# ExternalMotorController.net
KiCad netlist of a schematic drawn in EAGLE
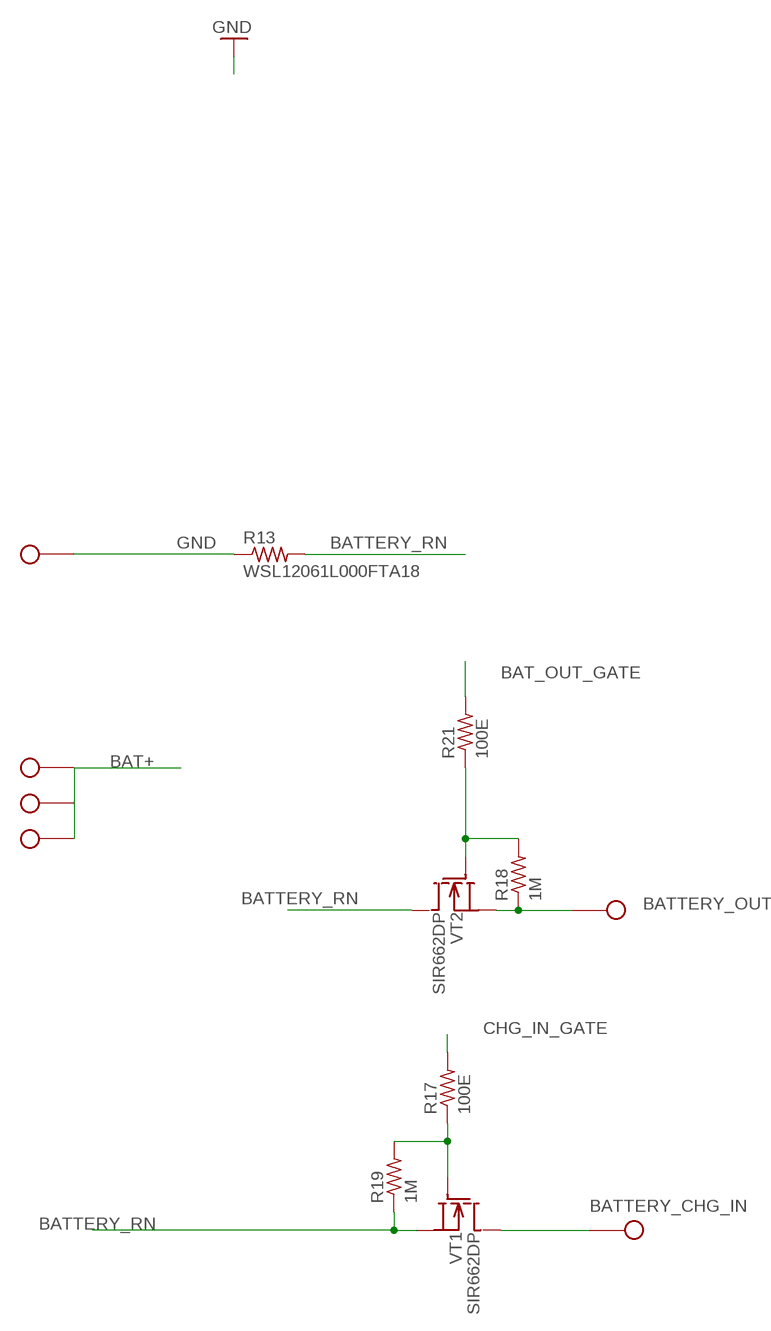
[diagram p0: schematic, sheet 1]
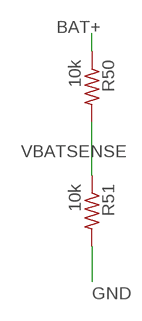
[diagram p1: schematic, sheet 3]
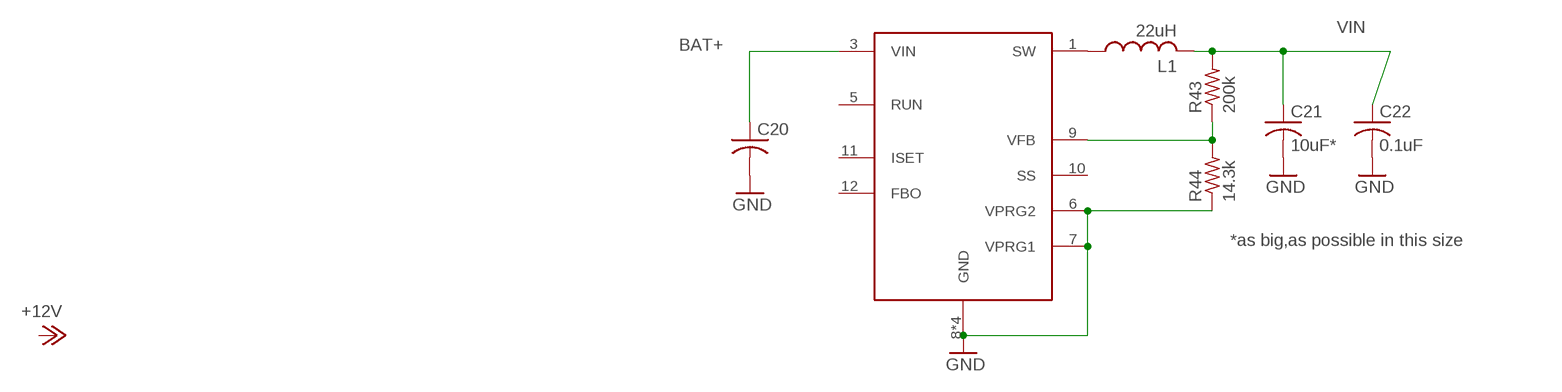
[diagram p2: schematic, sheet 4]
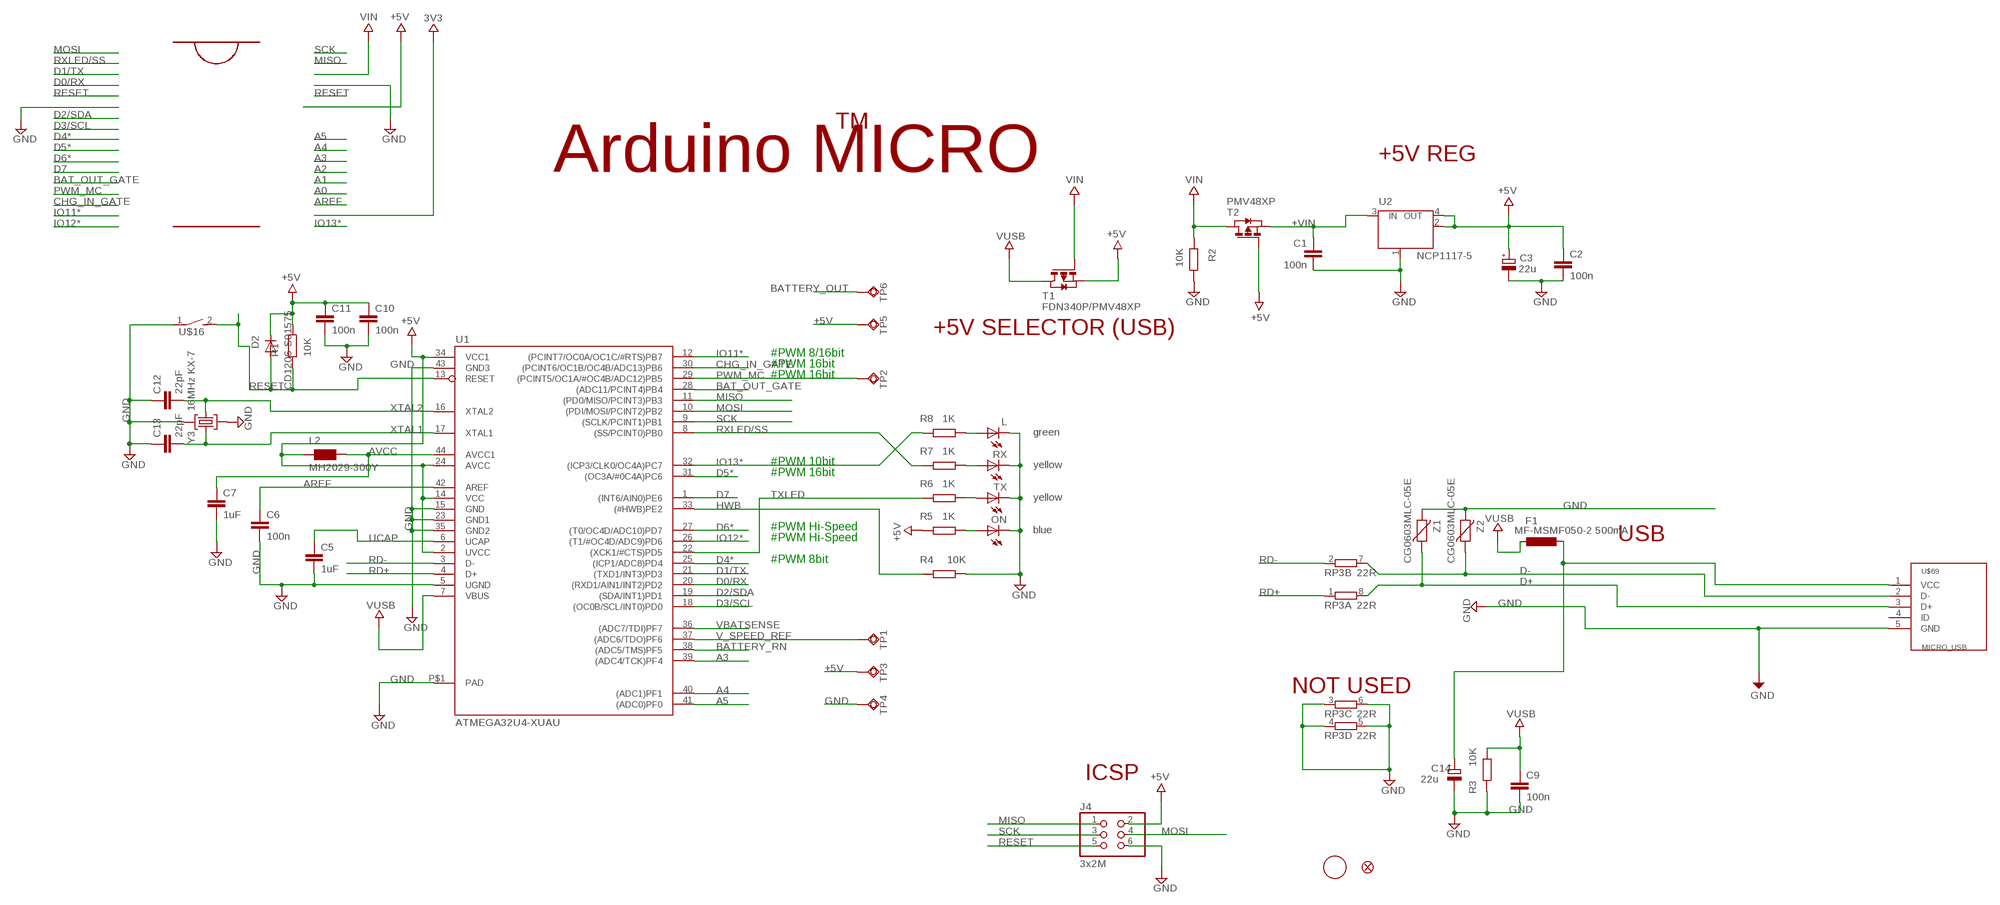
[diagram p3: schematic, sheet 5]

(export (version "E")
  (design (tool "Eeschema 10.0.6"))
  (components
    (comp (ref "R13")
      (value "WSL12061L000FTA18")
      (footprint "eagle-import:R2512")
      (libsource (lib "eagle-import") (part "R-US_R2512"))
    )
    (comp (ref "R17")
      (value "100E")
      (footprint "eagle-import:R0402")
      (libsource (lib "eagle-import") (part "R-US_R0402"))
    )
    (comp (ref "R18")
      (value "1M")
      (footprint "eagle-import:R0402")
      (libsource (lib "eagle-import") (part "R-US_R0402"))
    )
    (comp (ref "R19")
      (value "1M")
      (footprint "eagle-import:R0402")
      (libsource (lib "eagle-import") (part "R-US_R0402"))
    )
    (comp (ref "R21")
      (value "100E")
      (footprint "eagle-import:R0402")
      (libsource (lib "eagle-import") (part "R-US_R0402"))
    )
    (comp (ref "VT1")
      (value "SIR662DP")
      (footprint "eagle-import:POWERPAK_SO8")
      (libsource (lib "eagle-import") (part "SIR662DP"))
    )
    (comp (ref "VT2")
      (value "SIR662DP")
      (footprint "eagle-import:POWERPAK_SO8")
      (libsource (lib "eagle-import") (part "SIR662DP"))
    )
    (comp (ref "X1")
      (value "SOLDER_HOLE18AWG")
      (footprint "eagle-import:SOLDER_HOLE_18")
      (libsource (lib "eagle-import") (part "SOLDER_HOLE18AWG"))
    )
    (comp (ref "X2")
      (value "SOLDER_HOLE18AWG")
      (footprint "eagle-import:SOLDER_HOLE_18")
      (libsource (lib "eagle-import") (part "SOLDER_HOLE18AWG"))
    )
    (comp (ref "X3")
      (value "SOLDER_HOLE18AWG")
      (footprint "eagle-import:SOLDER_HOLE_18")
      (libsource (lib "eagle-import") (part "SOLDER_HOLE18AWG"))
    )
    (comp (ref "X4")
      (value "SOLDER_HOLE18AWG")
      (footprint "eagle-import:SOLDER_HOLE_18")
      (libsource (lib "eagle-import") (part "SOLDER_HOLE18AWG"))
    )
    (comp (ref "X5")
      (value "SOLDER_HOLE18AWG")
      (footprint "eagle-import:SOLDER_HOLE_18")
      (libsource (lib "eagle-import") (part "SOLDER_HOLE18AWG"))
    )
    (comp (ref "X13")
      (value "SOLDER_HOLE18AWG")
      (footprint "eagle-import:SOLDER_HOLE_18")
      (libsource (lib "eagle-import") (part "SOLDER_HOLE18AWG"))
    )
    (comp (ref "C1")
      (value "100n")
      (footprint "eagle-import:C0402")
      (libsource (lib "eagle-import") (part "C-EUC0402"))
    )
    (comp (ref "C2")
      (value "100n")
      (footprint "eagle-import:C0402")
      (libsource (lib "eagle-import") (part "C-EUC0402"))
    )
    (comp (ref "C3")
      (value "22u")
      (footprint "eagle-import:SMC_B")
      (libsource (lib "eagle-import") (part "CPOL-EUSMCB"))
    )
    (comp (ref "C5")
      (value "1uF")
      (footprint "eagle-import:C0402")
      (libsource (lib "eagle-import") (part "C-EUC0402"))
    )
    (comp (ref "C6")
      (value "100n")
      (footprint "eagle-import:C0402")
      (libsource (lib "eagle-import") (part "C-EUC0402"))
    )
    (comp (ref "C7")
      (value "1uF")
      (footprint "eagle-import:C0402")
      (libsource (lib "eagle-import") (part "C-EUC0402"))
    )
    (comp (ref "C9")
      (value "100n")
      (footprint "eagle-import:C0402")
      (libsource (lib "eagle-import") (part "C-EUC0402"))
    )
    (comp (ref "C10")
      (value "100n")
      (footprint "eagle-import:C0402")
      (libsource (lib "eagle-import") (part "C-EUC0402"))
    )
    (comp (ref "C11")
      (value "100n")
      (footprint "eagle-import:C0402")
      (libsource (lib "eagle-import") (part "C-EUC0402"))
    )
    (comp (ref "C12")
      (value "22pF")
      (footprint "eagle-import:C0402")
      (libsource (lib "eagle-import") (part "C-EUC0402"))
    )
    (comp (ref "C13")
      (value "22pF")
      (footprint "eagle-import:C0402")
      (libsource (lib "eagle-import") (part "C-EUC0402"))
    )
    (comp (ref "C14")
      (value "22u")
      (footprint "eagle-import:SMC_B")
      (libsource (lib "eagle-import") (part "CPOL-EUSMCB"))
    )
    (comp (ref "D2")
      (value "CD1206-S01575")
      (footprint "eagle-import:MINIMELF")
      (libsource (lib "eagle-import") (part "DIODE-MINIMELF"))
    )
    (comp (ref "F1")
      (value "MF-MSMF050-2 500mA")
      (footprint "eagle-import:L1812")
      (libsource (lib "eagle-import") (part "L-EUL1812"))
    )
    (comp (ref "J4")
      (value "3x2M")
      (footprint "eagle-import:2X03")
      (libsource (lib "eagle-import") (part "PINHD-2X3"))
    )
    (comp (ref "L")
      (value "green")
      (footprint "eagle-import:CHIPLED_0805")
      (libsource (lib "eagle-import") (part "LEDCHIPLED_0805"))
    )
    (comp (ref "L2")
      (value "MH2029-300Y")
      (footprint "eagle-import:0805")
      (libsource (lib "eagle-import") (part "WE-CBF_0805"))
    )
    (comp (ref "ON")
      (value "blue")
      (footprint "eagle-import:CHIPLED_0805")
      (libsource (lib "eagle-import") (part "LEDCHIPLED_0805"))
    )
    (comp (ref "R1")
      (value "10K")
      (footprint "eagle-import:R0402")
      (libsource (lib "eagle-import") (part "R-EU_R0402"))
    )
    (comp (ref "R2")
      (value "10K")
      (footprint "eagle-import:R0402")
      (libsource (lib "eagle-import") (part "R-EU_R0402"))
    )
    (comp (ref "R3")
      (value "10K")
      (footprint "eagle-import:R0402")
      (libsource (lib "eagle-import") (part "R-EU_R0402"))
    )
    (comp (ref "R4")
      (value "10K")
      (footprint "eagle-import:R0402")
      (libsource (lib "eagle-import") (part "R-EU_R0402"))
    )
    (comp (ref "R5")
      (value "1K")
      (footprint "eagle-import:R0402")
      (libsource (lib "eagle-import") (part "R-EU_R0402"))
    )
    (comp (ref "R6")
      (value "1K")
      (footprint "eagle-import:R0402")
      (libsource (lib "eagle-import") (part "R-EU_R0402"))
    )
    (comp (ref "R7")
      (value "1K")
      (footprint "eagle-import:R0402")
      (libsource (lib "eagle-import") (part "R-EU_R0402"))
    )
    (comp (ref "R8")
      (value "1K")
      (footprint "eagle-import:R0402")
      (libsource (lib "eagle-import") (part "R-EU_R0402"))
    )
    (comp (ref "RP3")
      (value "22R")
      (footprint "eagle-import:CAY16")
      (libsource (lib "eagle-import") (part "4R-NCAY16"))
    )
    (comp (ref "RX")
      (value "yellow")
      (footprint "eagle-import:CHIPLED_0805")
      (libsource (lib "eagle-import") (part "LEDCHIPLED_0805"))
    )
    (comp (ref "T1")
      (value "FDN340P/PMV48XP")
      (footprint "eagle-import:SOT-23")
      (libsource (lib "eagle-import") (part "PMOSSOT23"))
    )
    (comp (ref "T2")
      (value "PMV48XP")
      (footprint "eagle-import:SOT-23")
      (libsource (lib "eagle-import") (part "PMOSSOT23"))
    )
    (comp (ref "TP1")
      (value "TPSQTP15SQ")
      (footprint "eagle-import:TP15SQ")
      (libsource (lib "eagle-import") (part "TPSQTP15SQ"))
    )
    (comp (ref "TP2")
      (value "TPSQTP15SQ")
      (footprint "eagle-import:TP15SQ")
      (libsource (lib "eagle-import") (part "TPSQTP15SQ"))
    )
    (comp (ref "TP3")
      (value "TPSQTP15SQ")
      (footprint "eagle-import:TP15SQ")
      (libsource (lib "eagle-import") (part "TPSQTP15SQ"))
    )
    (comp (ref "TP4")
      (value "TPSQTP15SQ")
      (footprint "eagle-import:TP15SQ")
      (libsource (lib "eagle-import") (part "TPSQTP15SQ"))
    )
    (comp (ref "TP5")
      (value "TPSQTP15SQ")
      (footprint "eagle-import:TP15SQ")
      (libsource (lib "eagle-import") (part "TPSQTP15SQ"))
    )
    (comp (ref "TP6")
      (value "TPSQTP15SQ")
      (footprint "eagle-import:TP15SQ")
      (libsource (lib "eagle-import") (part "TPSQTP15SQ"))
    )
    (comp (ref "TX")
      (value "yellow")
      (footprint "eagle-import:CHIPLED_0805")
      (libsource (lib "eagle-import") (part "LEDCHIPLED_0805"))
    )
    (comp (ref "U$16")
      (value "RGHT-ANGLE-SMT-SWITCH-688-SKRELF")
      (footprint "eagle-import:2.9X3.9X2.0")
      (libsource (lib "eagle-import") (part "RGHT-ANGLE-SMT-SWITCH-688-SKRELF"))
    )
    (comp (ref "U$37")
      (value "FIDUCIALMOUNT")
      (footprint "eagle-import:FIDUCIA-MOUNT")
      (libsource (lib "eagle-import") (part "FIDUCIALMOUNT"))
    )
    (comp (ref "U$53")
      (value "FIDUCIAL1X2")
      (footprint "eagle-import:FIDUCIAL-1X2")
      (libsource (lib "eagle-import") (part "FIDUCIAL1X2"))
    )
    (comp (ref "U$69")
      (value "MICRO_USB")
      (footprint "eagle-import:MICRO_USB")
      (libsource (lib "eagle-import") (part "MICRO_USB"))
    )
    (comp (ref "U1")
      (value "ATMEGA32U4-XUAU")
      (footprint "eagle-import:TQFP44-PAD")
      (libsource (lib "eagle-import") (part "ATMEGA32U4-XUAU"))
    )
    (comp (ref "U2")
      (value "NCP1117-5")
      (footprint "eagle-import:LINEAR_SOT223")
      (libsource (lib "eagle-import") (part "LINEAR_MC33269ST"))
    )
    (comp (ref "Y3")
      (value "16MHz KX-7")
      (footprint "eagle-import:CRYSTAL-3.2-2.5")
      (libsource (lib "eagle-import") (part "CRYSTAL-3.2-2.5"))
    )
    (comp (ref "Z1")
      (value "CG0603MLC-05E")
      (footprint "eagle-import:CT_CN0603")
      (libsource (lib "eagle-import") (part "VARISTORCN0603"))
    )
    (comp (ref "Z2")
      (value "CG0603MLC-05E")
      (footprint "eagle-import:CT_CN0603")
      (libsource (lib "eagle-import") (part "VARISTORCN0603"))
    )
    (comp (ref "C20")
      (value "RCL_C-USC0805")
      (footprint "eagle-import:RCL_C0805$1")
      (libsource (lib "eagle-import") (part "RCL_C-USC0805"))
    )
    (comp (ref "C21")
      (value "10uF*")
      (footprint "eagle-import:RCL_C4532$1")
      (libsource (lib "eagle-import") (part "RCL_C-USC4532"))
    )
    (comp (ref "C22")
      (value "0.1uF")
      (footprint "eagle-import:C0402")
      (libsource (lib "eagle-import") (part "C-USC0402"))
    )
    (comp (ref "DA2")
      (value "LTC3630")
      (footprint "eagle-import:MSE16(12)")
      (libsource (lib "eagle-import") (part "LTC3630"))
    )
    (comp (ref "L1")
      (value "22uH")
      (footprint "eagle-import:M-PAD-2.1_1210")
      (libsource (lib "eagle-import") (part "M-PAD-2.1_L_USD"))
    )
    (comp (ref "R43")
      (value "200k")
      (footprint "eagle-import:RCL_R0402")
      (libsource (lib "eagle-import") (part "RCL_R-US_R0402"))
    )
    (comp (ref "R44")
      (value "14.3k")
      (footprint "eagle-import:RCL_R0402")
      (libsource (lib "eagle-import") (part "RCL_R-US_R0402"))
    )
    (comp (ref "R50")
      (value "10k")
      (footprint "eagle-import:R0402")
      (libsource (lib "eagle-import") (part "rcl_R-US_R0402"))
    )
    (comp (ref "R51")
      (value "10k")
      (footprint "eagle-import:R0402")
      (libsource (lib "eagle-import") (part "rcl_R-US_R0402"))
    )
  )
  (nets
    (net (code "1") (name "+5V") (class "Default")
      (node (ref "C10") (pin "1") (pinfunction "1_1") (pintype "passive"))
      (node (ref "C11") (pin "1") (pinfunction "1_1") (pintype "passive"))
      (node (ref "C2") (pin "1") (pinfunction "1_1") (pintype "passive"))
      (node (ref "C3") (pin "+") (pinfunction "+_+") (pintype "passive"))
      (node (ref "D2") (pin "C") (pinfunction "C_C") (pintype "passive"))
      (node (ref "J4") (pin "2") (pinfunction "2_2") (pintype "passive"))
      (node (ref "L2") (pin "1") (pinfunction "1_1") (pintype "passive"))
      (node (ref "R1") (pin "1") (pinfunction "1_1") (pintype "passive"))
      (node (ref "R5") (pin "1") (pinfunction "1_1") (pintype "passive"))
      (node (ref "T1") (pin "2") (pinfunction "S_2") (pintype "passive"))
      (node (ref "T2") (pin "3") (pinfunction "G_3") (pintype "passive"))
      (node (ref "TP3") (pin "TP") (pinfunction "TP_TP") (pintype "input"))
      (node (ref "TP5") (pin "TP") (pinfunction "TP_TP") (pintype "input"))
      (node (ref "U1") (pin "14") (pinfunction "VCC_14") (pintype "power_in"))
      (node (ref "U1") (pin "2") (pinfunction "UVCC_2") (pintype "power_in"))
      (node (ref "U1") (pin "24") (pinfunction "AVCC_24") (pintype "power_in"))
      (node (ref "U1") (pin "34") (pinfunction "VCC1_34") (pintype "power_in"))
      (node (ref "U2") (pin "2") (pinfunction "OUT_2") (pintype "passive"))
      (node (ref "U2") (pin "4") (pinfunction "OUT_4") (pintype "passive"))
    )
    (net (code "3") (name "+VIN") (class "Default")
      (node (ref "C1") (pin "1") (pinfunction "1_1") (pintype "passive"))
      (node (ref "T2") (pin "2") (pinfunction "S_2") (pintype "passive"))
      (node (ref "U2") (pin "3") (pinfunction "IN_3") (pintype "input"))
    )
    (net (code "8") (name "A3") (class "Default")
      (node (ref "U1") (pin "39") (pinfunction "(ADC4/TCK)PF4_39") (pintype "bidirectional"))
    )
    (net (code "9") (name "A4") (class "Default")
      (node (ref "U1") (pin "40") (pinfunction "(ADC1)PF1_40") (pintype "bidirectional"))
    )
    (net (code "10") (name "A5") (class "Default")
      (node (ref "U1") (pin "41") (pinfunction "(ADC0)PF0_41") (pintype "bidirectional"))
    )
    (net (code "11") (name "AREF") (class "Default")
      (node (ref "C6") (pin "1") (pinfunction "1_1") (pintype "passive"))
      (node (ref "U1") (pin "42") (pinfunction "AREF_42") (pintype "power_in"))
    )
    (net (code "12") (name "AVCC") (class "Default")
      (node (ref "C7") (pin "1") (pinfunction "1_1") (pintype "passive"))
      (node (ref "L2") (pin "2") (pinfunction "2_2") (pintype "passive"))
      (node (ref "U1") (pin "44") (pinfunction "AVCC1_44") (pintype "power_in"))
    )
    (net (code "13") (name "BAT+") (class "Default")
      (node (ref "C20") (pin "1") (pinfunction "1_1") (pintype "passive"))
      (node (ref "DA2") (pin "3") (pinfunction "VIN_3") (pintype "power_in"))
      (node (ref "R50") (pin "1") (pinfunction "1_1") (pintype "passive"))
      (node (ref "X1") (pin "1") (pinfunction "P$1_1") (pintype "bidirectional"))
      (node (ref "X4") (pin "1") (pinfunction "P$1_1") (pintype "bidirectional"))
      (node (ref "X5") (pin "1") (pinfunction "P$1_1") (pintype "bidirectional"))
    )
    (net (code "14") (name "BATTERY_CHG_IN") (class "Default")
      (node (ref "VT1") (pin "D") (pinfunction "D_D") (pintype "bidirectional"))
      (node (ref "X2") (pin "1") (pinfunction "P$1_1") (pintype "bidirectional"))
    )
    (net (code "15") (name "BATTERY_OUT") (class "Default")
      (node (ref "R18") (pin "1") (pinfunction "1_1") (pintype "passive"))
      (node (ref "TP6") (pin "TP") (pinfunction "TP_TP") (pintype "input"))
      (node (ref "VT2") (pin "S1") (pinfunction "S_S1") (pintype "bidirectional"))
      (node (ref "VT2") (pin "S2") (pinfunction "S_S2") (pintype "bidirectional"))
      (node (ref "VT2") (pin "S3") (pinfunction "S_S3") (pintype "bidirectional"))
      (node (ref "X3") (pin "1") (pinfunction "P$1_1") (pintype "bidirectional"))
    )
    (net (code "16") (name "BATTERY_RN") (class "Default")
      (node (ref "R13") (pin "2") (pinfunction "2_2") (pintype "passive"))
      (node (ref "R19") (pin "1") (pinfunction "1_1") (pintype "passive"))
      (node (ref "U1") (pin "38") (pinfunction "(ADC5/TMS)PF5_38") (pintype "bidirectional"))
      (node (ref "VT1") (pin "S1") (pinfunction "S_S1") (pintype "bidirectional"))
      (node (ref "VT1") (pin "S2") (pinfunction "S_S2") (pintype "bidirectional"))
      (node (ref "VT1") (pin "S3") (pinfunction "S_S3") (pintype "bidirectional"))
      (node (ref "VT2") (pin "D") (pinfunction "D_D") (pintype "bidirectional"))
    )
    (net (code "17") (name "BAT_OUT_GATE") (class "Default")
      (node (ref "R21") (pin "2") (pinfunction "2_2") (pintype "passive"))
      (node (ref "U1") (pin "28") (pinfunction "(ADC11/PCINT4)PB4_28") (pintype "bidirectional"))
    )
    (net (code "18") (name "CHG_IN_GATE") (class "Default")
      (node (ref "R17") (pin "2") (pinfunction "2_2") (pintype "passive"))
      (node (ref "U1") (pin "30") (pinfunction "(PCINT6/OC1B/OC4B/ADC13)PB6_30") (pintype "bidirectional"))
    )
    (net (code "19") (name "D+") (class "Default")
      (node (ref "RP3") (pin "8") (pinfunction "2_8") (pintype "passive"))
      (node (ref "U$69") (pin "3") (pinfunction "D+_3") (pintype "bidirectional"))
      (node (ref "Z1") (pin "1") (pinfunction "1_1") (pintype "passive"))
    )
    (net (code "20") (name "D-") (class "Default")
      (node (ref "RP3") (pin "7") (pinfunction "2_7") (pintype "passive"))
      (node (ref "U$69") (pin "2") (pinfunction "D-_2") (pintype "bidirectional"))
      (node (ref "Z2") (pin "1") (pinfunction "1_1") (pintype "passive"))
    )
    (net (code "21") (name "D0{slash}RX") (class "Default")
      (node (ref "U1") (pin "20") (pinfunction "(RXD1/AIN1/INT2)PD2_20") (pintype "bidirectional"))
    )
    (net (code "22") (name "D1{slash}TX") (class "Default")
      (node (ref "U1") (pin "21") (pinfunction "(TXD1/INT3)PD3_21") (pintype "bidirectional"))
    )
    (net (code "23") (name "D2{slash}SDA") (class "Default")
      (node (ref "U1") (pin "19") (pinfunction "(SDA/INT1)PD1_19") (pintype "bidirectional"))
    )
    (net (code "24") (name "D3{slash}SCL") (class "Default")
      (node (ref "U1") (pin "18") (pinfunction "(OC0B/SCL/INT0)PD0_18") (pintype "bidirectional"))
    )
    (net (code "25") (name "D4*") (class "Default")
      (node (ref "U1") (pin "25") (pinfunction "(ICP1/ADC8)PD4_25") (pintype "bidirectional"))
    )
    (net (code "26") (name "D5*") (class "Default")
      (node (ref "U1") (pin "31") (pinfunction "(OC3A/#0C4A)PC6_31") (pintype "bidirectional"))
    )
    (net (code "27") (name "D6*") (class "Default")
      (node (ref "U1") (pin "27") (pinfunction "(T0/OC4D/ADC10)PD7_27") (pintype "bidirectional"))
    )
    (net (code "28") (name "D7") (class "Default")
      (node (ref "U1") (pin "1") (pinfunction "(INT6/AIN0)PE6_1") (pintype "bidirectional"))
    )
    (net (code "29") (name "GND") (class "Default")
      (node (ref "C1") (pin "2") (pinfunction "2_2") (pintype "passive"))
      (node (ref "C10") (pin "2") (pinfunction "2_2") (pintype "passive"))
      (node (ref "C11") (pin "2") (pinfunction "2_2") (pintype "passive"))
      (node (ref "C12") (pin "1") (pinfunction "1_1") (pintype "passive"))
      (node (ref "C13") (pin "1") (pinfunction "1_1") (pintype "passive"))
      (node (ref "C14") (pin "-") (pinfunction "-_-") (pintype "passive"))
      (node (ref "C2") (pin "2") (pinfunction "2_2") (pintype "passive"))
      (node (ref "C20") (pin "2") (pinfunction "2_2") (pintype "passive"))
      (node (ref "C21") (pin "2") (pinfunction "2_2") (pintype "passive"))
      (node (ref "C22") (pin "2") (pinfunction "2_2") (pintype "passive"))
      (node (ref "C3") (pin "-") (pinfunction "-_-") (pintype "passive"))
      (node (ref "C5") (pin "2") (pinfunction "2_2") (pintype "passive"))
      (node (ref "C6") (pin "2") (pinfunction "2_2") (pintype "passive"))
      (node (ref "C7") (pin "2") (pinfunction "2_2") (pintype "passive"))
      (node (ref "C9") (pin "2") (pinfunction "2_2") (pintype "passive"))
      (node (ref "DA2") (pin "14") (pinfunction "GND_14") (pintype "bidirectional"))
      (node (ref "DA2") (pin "16") (pinfunction "GND_16") (pintype "bidirectional"))
      (node (ref "DA2") (pin "17") (pinfunction "GND_17") (pintype "bidirectional"))
      (node (ref "DA2") (pin "6") (pinfunction "VPRG2_6") (pintype "input"))
      (node (ref "DA2") (pin "7") (pinfunction "VPRG1_7") (pintype "input"))
      (node (ref "DA2") (pin "8") (pinfunction "GND_8") (pintype "bidirectional"))
      (node (ref "J4") (pin "6") (pinfunction "6_6") (pintype "passive"))
      (node (ref "L") (pin "C") (pinfunction "C_C") (pintype "passive"))
      (node (ref "ON") (pin "C") (pinfunction "C_C") (pintype "passive"))
      (node (ref "R13") (pin "1") (pinfunction "1_1") (pintype "passive"))
      (node (ref "R2") (pin "1") (pinfunction "1_1") (pintype "passive"))
      (node (ref "R3") (pin "1") (pinfunction "1_1") (pintype "passive"))
      (node (ref "R4") (pin "2") (pinfunction "2_2") (pintype "passive"))
      (node (ref "R44") (pin "1") (pinfunction "1_1") (pintype "passive"))
      (node (ref "R51") (pin "2") (pinfunction "2_2") (pintype "passive"))
      (node (ref "RP3") (pin "3") (pinfunction "1_3") (pintype "passive"))
      (node (ref "RP3") (pin "4") (pinfunction "1_4") (pintype "passive"))
      (node (ref "RP3") (pin "5") (pinfunction "2_5") (pintype "passive"))
      (node (ref "RP3") (pin "6") (pinfunction "2_6") (pintype "passive"))
      (node (ref "RX") (pin "C") (pinfunction "C_C") (pintype "passive"))
      (node (ref "TP4") (pin "TP") (pinfunction "TP_TP") (pintype "input"))
      (node (ref "TX") (pin "C") (pinfunction "C_C") (pintype "passive"))
      (node (ref "U$16") (pin "1") (pinfunction "1_1") (pintype "passive"))
      (node (ref "U$69") (pin "5") (pinfunction "GND_5") (pintype "bidirectional"))
      (node (ref "U1") (pin "15") (pinfunction "GND_15") (pintype "power_in"))
      (node (ref "U1") (pin "23") (pinfunction "GND1_23") (pintype "power_in"))
      (node (ref "U1") (pin "35") (pinfunction "GND2_35") (pintype "power_in"))
      (node (ref "U1") (pin "43") (pinfunction "GND3_43") (pintype "power_in"))
      (node (ref "U1") (pin "5") (pinfunction "UGND_5") (pintype "power_in"))
      (node (ref "U1") (pin "P$1") (pinfunction "PAD_P$1") (pintype "power_in"))
      (node (ref "U2") (pin "1") (pinfunction "GND/ADJ_1") (pintype "input"))
      (node (ref "X13") (pin "1") (pinfunction "P$1_1") (pintype "bidirectional"))
      (node (ref "Y3") (pin "2") (pinfunction "GND_2") (pintype "passive"))
      (node (ref "Y3") (pin "4") (pinfunction "GND_4") (pintype "passive"))
      (node (ref "Z1") (pin "2") (pinfunction "2_2") (pintype "passive"))
      (node (ref "Z2") (pin "2") (pinfunction "2_2") (pintype "passive"))
    )
    (net (code "30") (name "HWB") (class "Default")
      (node (ref "R4") (pin "1") (pinfunction "1_1") (pintype "passive"))
      (node (ref "U1") (pin "33") (pinfunction "(#HWB)PE2_33") (pintype "bidirectional"))
    )
    (net (code "31") (name "IO11*") (class "Default")
      (node (ref "U1") (pin "12") (pinfunction "(PCINT7/OC0A/OC1C/#RTS)PB7_12") (pintype "bidirectional"))
    )
    (net (code "32") (name "IO12*") (class "Default")
      (node (ref "U1") (pin "26") (pinfunction "(T1/#OC4D/ADC9)PD6_26") (pintype "bidirectional"))
    )
    (net (code "33") (name "IO13*") (class "Default")
      (node (ref "R8") (pin "1") (pinfunction "1_1") (pintype "passive"))
      (node (ref "U1") (pin "32") (pinfunction "(ICP3/CLK0/OC4A)PC7_32") (pintype "bidirectional"))
    )
    (net (code "34") (name "MISO") (class "Default")
      (node (ref "J4") (pin "1") (pinfunction "1_1") (pintype "passive"))
      (node (ref "U1") (pin "11") (pinfunction "(PD0/MISO/PCINT3)PB3_11") (pintype "bidirectional"))
    )
    (net (code "35") (name "MOSI") (class "Default")
      (node (ref "J4") (pin "4") (pinfunction "4_4") (pintype "passive"))
      (node (ref "U1") (pin "10") (pinfunction "(PDI/MOSI/PCINT2)PB2_10") (pintype "bidirectional"))
    )
    (net (code "36") (name "Net-(DA2-SW)") (class "Default")
      (node (ref "DA2") (pin "1") (pinfunction "SW_1") (pintype "power_in"))
      (node (ref "L1") (pin "1") (pinfunction "1_1") (pintype "passive"))
    )
    (net (code "37") (name "Net-(DA2-VFB)") (class "Default")
      (node (ref "DA2") (pin "9") (pinfunction "VFB_9") (pintype "input"))
      (node (ref "R43") (pin "1") (pinfunction "1_1") (pintype "passive"))
      (node (ref "R44") (pin "2") (pinfunction "2_2") (pintype "passive"))
    )
    (net (code "38") (name "Net-(L-PadA)") (class "Default")
      (node (ref "L") (pin "A") (pinfunction "A_A") (pintype "passive"))
      (node (ref "R8") (pin "2") (pinfunction "2_2") (pintype "passive"))
    )
    (net (code "39") (name "Net-(ON-PadA)") (class "Default")
      (node (ref "ON") (pin "A") (pinfunction "A_A") (pintype "passive"))
      (node (ref "R5") (pin "2") (pinfunction "2_2") (pintype "passive"))
    )
    (net (code "40") (name "Net-(R6-Pad2)") (class "Default")
      (node (ref "R6") (pin "2") (pinfunction "2_2") (pintype "passive"))
      (node (ref "TX") (pin "A") (pinfunction "A_A") (pintype "passive"))
    )
    (net (code "41") (name "Net-(R7-Pad2)") (class "Default")
      (node (ref "R7") (pin "2") (pinfunction "2_2") (pintype "passive"))
      (node (ref "RX") (pin "A") (pinfunction "A_A") (pintype "passive"))
    )
    (net (code "42") (name "Net-(R17-Pad1)") (class "Default")
      (node (ref "R17") (pin "1") (pinfunction "1_1") (pintype "passive"))
      (node (ref "R19") (pin "2") (pinfunction "2_2") (pintype "passive"))
      (node (ref "VT1") (pin "G") (pinfunction "G_G") (pintype "bidirectional"))
    )
    (net (code "43") (name "Net-(R18-Pad2)") (class "Default")
      (node (ref "R18") (pin "2") (pinfunction "2_2") (pintype "passive"))
      (node (ref "R21") (pin "1") (pinfunction "1_1") (pintype "passive"))
      (node (ref "VT2") (pin "G") (pinfunction "G_G") (pintype "bidirectional"))
    )
    (net (code "44") (name "Net-(U$69-VCC)") (class "Default")
      (node (ref "C14") (pin "+") (pinfunction "+_+") (pintype "passive"))
      (node (ref "F1") (pin "1") (pinfunction "1_1") (pintype "passive"))
      (node (ref "U$69") (pin "1") (pinfunction "VCC_1") (pintype "bidirectional"))
    )
    (net (code "45") (name "PWM_MC") (class "Default")
      (node (ref "TP2") (pin "TP") (pinfunction "TP_TP") (pintype "input"))
      (node (ref "U1") (pin "29") (pinfunction "(PCINT5/OC1A/#OC4B/ADC12)PB5_29") (pintype "bidirectional"))
    )
    (net (code "46") (name "RD+") (class "Default")
      (node (ref "RP3") (pin "1") (pinfunction "1_1") (pintype "passive"))
      (node (ref "U1") (pin "4") (pinfunction "D+_4") (pintype "bidirectional"))
    )
    (net (code "47") (name "RD-") (class "Default")
      (node (ref "RP3") (pin "2") (pinfunction "1_2") (pintype "passive"))
      (node (ref "U1") (pin "3") (pinfunction "D-_3") (pintype "bidirectional"))
    )
    (net (code "48") (name "RESET") (class "Default")
      (node (ref "D2") (pin "A") (pinfunction "A_A") (pintype "passive"))
      (node (ref "J4") (pin "5") (pinfunction "5_5") (pintype "passive"))
      (node (ref "R1") (pin "2") (pinfunction "2_2") (pintype "passive"))
      (node (ref "U$16") (pin "2") (pinfunction "2_2") (pintype "passive"))
      (node (ref "U1") (pin "13") (pinfunction "RESET_13") (pintype "input"))
    )
    (net (code "49") (name "RXLED{slash}SS") (class "Default")
      (node (ref "R7") (pin "1") (pinfunction "1_1") (pintype "passive"))
      (node (ref "U1") (pin "8") (pinfunction "(SS/PCINT0)PB0_8") (pintype "bidirectional"))
    )
    (net (code "50") (name "SCK") (class "Default")
      (node (ref "J4") (pin "3") (pinfunction "3_3") (pintype "passive"))
      (node (ref "U1") (pin "9") (pinfunction "(SCLK/PCINT1)PB1_9") (pintype "bidirectional"))
    )
    (net (code "51") (name "TXLED") (class "Default")
      (node (ref "R6") (pin "1") (pinfunction "1_1") (pintype "passive"))
      (node (ref "U1") (pin "22") (pinfunction "(XCK1/#CTS)PD5_22") (pintype "bidirectional"))
    )
    (net (code "52") (name "UCAP") (class "Default")
      (node (ref "C5") (pin "1") (pinfunction "1_1") (pintype "passive"))
      (node (ref "U1") (pin "6") (pinfunction "UCAP_6") (pintype "passive"))
    )
    (net (code "53") (name "VBATSENSE") (class "Default")
      (node (ref "R50") (pin "2") (pinfunction "2_2") (pintype "passive"))
      (node (ref "R51") (pin "1") (pinfunction "1_1") (pintype "passive"))
      (node (ref "U1") (pin "36") (pinfunction "(ADC7/TDI)PF7_36") (pintype "bidirectional"))
    )
    (net (code "54") (name "VIN") (class "Default")
      (node (ref "C21") (pin "1") (pinfunction "1_1") (pintype "passive"))
      (node (ref "C22") (pin "1") (pinfunction "1_1") (pintype "passive"))
      (node (ref "L1") (pin "2") (pinfunction "2_2") (pintype "passive"))
      (node (ref "R2") (pin "2") (pinfunction "2_2") (pintype "passive"))
      (node (ref "R43") (pin "2") (pinfunction "2_2") (pintype "passive"))
      (node (ref "T1") (pin "3") (pinfunction "G_3") (pintype "passive"))
      (node (ref "T2") (pin "1") (pinfunction "D_1") (pintype "passive"))
    )
    (net (code "55") (name "VUSB") (class "Default")
      (node (ref "C9") (pin "1") (pinfunction "1_1") (pintype "passive"))
      (node (ref "F1") (pin "2") (pinfunction "2_2") (pintype "passive"))
      (node (ref "R3") (pin "2") (pinfunction "2_2") (pintype "passive"))
      (node (ref "T1") (pin "1") (pinfunction "D_1") (pintype "passive"))
      (node (ref "U1") (pin "7") (pinfunction "VBUS_7") (pintype "input"))
    )
    (net (code "56") (name "V_SPEED_REF") (class "Default")
      (node (ref "TP1") (pin "TP") (pinfunction "TP_TP") (pintype "input"))
      (node (ref "U1") (pin "37") (pinfunction "(ADC6/TDO)PF6_37") (pintype "bidirectional"))
    )
    (net (code "57") (name "XTAL1") (class "Default")
      (node (ref "C13") (pin "2") (pinfunction "2_2") (pintype "passive"))
      (node (ref "U1") (pin "17") (pinfunction "XTAL1_17") (pintype "bidirectional"))
      (node (ref "Y3") (pin "3") (pinfunction "C2_3") (pintype "passive"))
    )
    (net (code "58") (name "XTAL2") (class "Default")
      (node (ref "C12") (pin "2") (pinfunction "2_2") (pintype "passive"))
      (node (ref "U1") (pin "16") (pinfunction "XTAL2_16") (pintype "bidirectional"))
      (node (ref "Y3") (pin "1") (pinfunction "C1_1") (pintype "passive"))
    )
    (net (code "59") (name "unconnected-(DA2-FBO-Pad12)") (class "Default")
      (node (ref "DA2") (pin "12") (pinfunction "FBO_12") (pintype "input"))
    )
    (net (code "60") (name "unconnected-(DA2-ISET-Pad11)") (class "Default")
      (node (ref "DA2") (pin "11") (pinfunction "ISET_11") (pintype "input"))
    )
    (net (code "61") (name "unconnected-(DA2-RUN-Pad5)") (class "Default")
      (node (ref "DA2") (pin "5") (pinfunction "RUN_5") (pintype "input"))
    )
    (net (code "62") (name "unconnected-(DA2-SS-Pad10)") (class "Default")
      (node (ref "DA2") (pin "10") (pinfunction "SS_10") (pintype "input"))
    )
    (net (code "63") (name "unconnected-(U$69-ID-Pad4)") (class "Default")
      (node (ref "U$69") (pin "4") (pinfunction "ID_4") (pintype "bidirectional"))
    )
  )
)
